# Versterker.net
KiCad netlist of a schematic drawn in Altium Designer
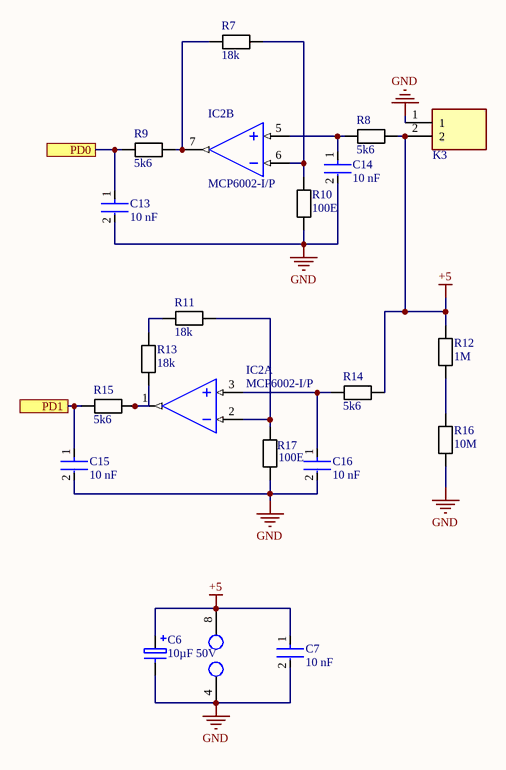
[diagram p0: Versterker.SchDoc]

(export (version "E")
  (design (tool "Eeschema 10.0.6"))
  (components
    (comp (ref "C6")
      (value "10µF 50V")
      (footprint "Elco 100uF 25V")
      (fields
        (field (name "PART NUMBER") "02015A270JAT2A")
        (field (name "MANUFACTURER") "AVX Interconnect / Elco")
      )
      (libsource (lib "schoolprojectcomponentlib") (part "Condensator Elco"))
    )
    (comp (ref "C7")
      (value "10 nF")
      (footprint "0805")
      (description "Chip Multilayer Ceramic Capacitors for General Purpose, 0805, 10uF, X5R, 15%, 10%, 25V")
      (fields (field (name "VOLTAGE") "25V") (field (name "TOLERANCE") "10%"))
      (libsource (lib "schoolprojectcomponentlib") (part "Condensator 0805"))
    )
    (comp (ref "C13")
      (value "10 nF")
      (footprint "0805")
      (description "Chip Multilayer Ceramic Capacitors for General Purpose, 0805, 10uF, X5R, 15%, 10%, 25V")
      (fields (field (name "VOLTAGE") "25V") (field (name "TOLERANCE") "10%"))
      (libsource (lib "schoolprojectcomponentlib") (part "Condensator 0805"))
    )
    (comp (ref "C14")
      (value "10 nF")
      (footprint "0805")
      (description "Chip Multilayer Ceramic Capacitors for General Purpose, 0805, 10uF, X5R, 15%, 10%, 25V")
      (fields (field (name "VOLTAGE") "25V") (field (name "TOLERANCE") "10%"))
      (libsource (lib "schoolprojectcomponentlib") (part "Condensator 0805"))
    )
    (comp (ref "C15")
      (value "10 nF")
      (footprint "0805")
      (description "Chip Multilayer Ceramic Capacitors for General Purpose, 0805, 10uF, X5R, 15%, 10%, 25V")
      (fields (field (name "VOLTAGE") "25V") (field (name "TOLERANCE") "10%"))
      (libsource (lib "schoolprojectcomponentlib") (part "Condensator 0805"))
    )
    (comp (ref "C16")
      (value "10 nF")
      (footprint "0805")
      (description "Chip Multilayer Ceramic Capacitors for General Purpose, 0805, 10uF, X5R, 15%, 10%, 25V")
      (fields (field (name "VOLTAGE") "25V") (field (name "TOLERANCE") "10%"))
      (libsource (lib "schoolprojectcomponentlib") (part "Condensator 0805"))
    )
    (comp (ref "IC2")
      (value "MCP6002-I/P")
      (footprint "Opamp")
      (description "AMP-OPA-MCP6002-IL8")
      (libsource (lib "") (part "Opamp_1"))
    )
    (comp (ref "K3")
      (value "282836-2")
      (footprint "Schroefconnector 2 Pin - duplicate")
      (description "Connector")
      (libsource (lib "schoolprojectcomponentlib") (part "Schroefconnector 2 Pin R"))
    )
    (comp (ref "R7")
      (value "18k")
      (footprint "weerstand")
      (fields (field (name "MANUFACTURER") "Vishay Dale") (field (name "PART NUMBER") "CRCW08050000Z0EA"))
      (libsource (lib "schoolprojectcomponentlib") (part "weerstand"))
    )
    (comp (ref "R8")
      (value "5k6")
      (footprint "weerstand")
      (fields (field (name "MANUFACTURER") "Vishay Dale") (field (name "PART NUMBER") "CRCW08050000Z0EA"))
      (libsource (lib "schoolprojectcomponentlib") (part "weerstand"))
    )
    (comp (ref "R9")
      (value "5k6")
      (footprint "weerstand")
      (fields (field (name "MANUFACTURER") "Vishay Dale") (field (name "PART NUMBER") "CRCW08050000Z0EA"))
      (libsource (lib "schoolprojectcomponentlib") (part "weerstand"))
    )
    (comp (ref "R10")
      (value "100E")
      (footprint "weerstand")
      (fields (field (name "MANUFACTURER") "Vishay Dale") (field (name "PART NUMBER") "CRCW08050000Z0EA"))
      (libsource (lib "schoolprojectcomponentlib") (part "weerstand"))
    )
    (comp (ref "R11")
      (value "18k")
      (footprint "weerstand")
      (fields (field (name "MANUFACTURER") "Vishay Dale") (field (name "PART NUMBER") "CRCW08050000Z0EA"))
      (libsource (lib "schoolprojectcomponentlib") (part "weerstand"))
    )
    (comp (ref "R12")
      (value "1M")
      (footprint "weerstand")
      (fields (field (name "MANUFACTURER") "Vishay Dale") (field (name "PART NUMBER") "CRCW08050000Z0EA"))
      (libsource (lib "schoolprojectcomponentlib") (part "weerstand"))
    )
    (comp (ref "R13")
      (value "18k")
      (footprint "weerstand")
      (fields (field (name "MANUFACTURER") "Vishay Dale") (field (name "PART NUMBER") "CRCW08050000Z0EA"))
      (libsource (lib "schoolprojectcomponentlib") (part "weerstand"))
    )
    (comp (ref "R14")
      (value "5k6")
      (footprint "weerstand")
      (fields (field (name "MANUFACTURER") "Vishay Dale") (field (name "PART NUMBER") "CRCW08050000Z0EA"))
      (libsource (lib "schoolprojectcomponentlib") (part "weerstand"))
    )
    (comp (ref "R15")
      (value "5k6")
      (footprint "weerstand")
      (fields (field (name "MANUFACTURER") "Vishay Dale") (field (name "PART NUMBER") "CRCW08050000Z0EA"))
      (libsource (lib "schoolprojectcomponentlib") (part "weerstand"))
    )
    (comp (ref "R16")
      (value "10M")
      (footprint "weerstand")
      (fields (field (name "MANUFACTURER") "Vishay Dale") (field (name "PART NUMBER") "CRCW08050000Z0EA"))
      (libsource (lib "schoolprojectcomponentlib") (part "weerstand"))
    )
    (comp (ref "R17")
      (value "100E")
      (footprint "weerstand")
      (fields (field (name "MANUFACTURER") "Vishay Dale") (field (name "PART NUMBER") "CRCW08050000Z0EA"))
      (libsource (lib "schoolprojectcomponentlib") (part "weerstand"))
    )
  )
  (nets
    (net (code "1") (name "+5") (class "Default")
      (node (ref "C6") (pin "1") (pinfunction "1_1") (pintype "passive"))
      (node (ref "C7") (pin "1") (pinfunction "1_1") (pintype "passive"))
      (node (ref "IC2") (pin "8") (pintype "power_in"))
      (node (ref "K3") (pin "2") (pinfunction "2_2") (pintype "passive"))
      (node (ref "R12") (pin "2") (pinfunction "2_2") (pintype "passive"))
      (node (ref "R14") (pin "2") (pinfunction "2_2") (pintype "passive"))
      (node (ref "R8") (pin "2") (pinfunction "2_2") (pintype "passive"))
    )
    (net (code "2") (name "/PD0") (class "Default")
      (node (ref "C13") (pin "1") (pinfunction "1_1") (pintype "passive"))
      (node (ref "R9") (pin "1") (pinfunction "1_1") (pintype "passive"))
    )
    (net (code "3") (name "/PD1") (class "Default")
      (node (ref "C15") (pin "1") (pinfunction "1_1") (pintype "passive"))
      (node (ref "R15") (pin "1") (pinfunction "1_1") (pintype "passive"))
    )
    (net (code "4") (name "GND") (class "Default")
      (node (ref "C13") (pin "2") (pinfunction "2_2") (pintype "passive"))
      (node (ref "C14") (pin "2") (pinfunction "2_2") (pintype "passive"))
      (node (ref "C15") (pin "2") (pinfunction "2_2") (pintype "passive"))
      (node (ref "C16") (pin "2") (pinfunction "2_2") (pintype "passive"))
      (node (ref "C6") (pin "2") (pinfunction "2_2") (pintype "passive"))
      (node (ref "C7") (pin "2") (pinfunction "2_2") (pintype "passive"))
      (node (ref "IC2") (pin "4") (pintype "power_in"))
      (node (ref "K3") (pin "1") (pinfunction "1_1") (pintype "passive"))
      (node (ref "R10") (pin "1") (pinfunction "1_1") (pintype "passive"))
      (node (ref "R16") (pin "1") (pinfunction "1_1") (pintype "passive"))
      (node (ref "R17") (pin "1") (pinfunction "1_1") (pintype "passive"))
    )
    (net (code "5") (name "Net-(C14-Pad1)") (class "Default")
      (node (ref "C14") (pin "1") (pinfunction "1_1") (pintype "passive"))
      (node (ref "IC2") (pin "5") (pintype "input"))
      (node (ref "R8") (pin "1") (pinfunction "1_1") (pintype "passive"))
    )
    (net (code "6") (name "Net-(C16-Pad1)") (class "Default")
      (node (ref "C16") (pin "1") (pinfunction "1_1") (pintype "passive"))
      (node (ref "IC2") (pin "3") (pintype "input"))
      (node (ref "R14") (pin "1") (pinfunction "1_1") (pintype "passive"))
    )
    (net (code "7") (name "Net-(IC2-Pad1)") (class "Default")
      (node (ref "IC2") (pin "1") (pintype "output"))
      (node (ref "R13") (pin "1") (pinfunction "1_1") (pintype "passive"))
      (node (ref "R15") (pin "2") (pinfunction "2_2") (pintype "passive"))
    )
    (net (code "8") (name "Net-(IC2-Pad2)") (class "Default")
      (node (ref "IC2") (pin "2") (pintype "input"))
      (node (ref "R11") (pin "2") (pinfunction "2_2") (pintype "passive"))
      (node (ref "R17") (pin "2") (pinfunction "2_2") (pintype "passive"))
    )
    (net (code "9") (name "Net-(IC2-Pad6)") (class "Default")
      (node (ref "IC2") (pin "6") (pintype "input"))
      (node (ref "R10") (pin "2") (pinfunction "2_2") (pintype "passive"))
      (node (ref "R7") (pin "2") (pinfunction "2_2") (pintype "passive"))
    )
    (net (code "10") (name "Net-(IC2-Pad7)") (class "Default")
      (node (ref "IC2") (pin "7") (pintype "output"))
      (node (ref "R7") (pin "1") (pinfunction "1_1") (pintype "passive"))
      (node (ref "R9") (pin "2") (pinfunction "2_2") (pintype "passive"))
    )
    (net (code "11") (name "Net-(R11-Pad1)") (class "Default")
      (node (ref "R11") (pin "1") (pinfunction "1_1") (pintype "passive"))
      (node (ref "R13") (pin "2") (pinfunction "2_2") (pintype "passive"))
    )
    (net (code "12") (name "Net-(R12-Pad1)") (class "Default")
      (node (ref "R12") (pin "1") (pinfunction "1_1") (pintype "passive"))
      (node (ref "R16") (pin "2") (pinfunction "2_2") (pintype "passive"))
    )
  )
)
